# skware-one-rev-arm-25-mini.net
KiCad netlist of a schematic drawn in EAGLE
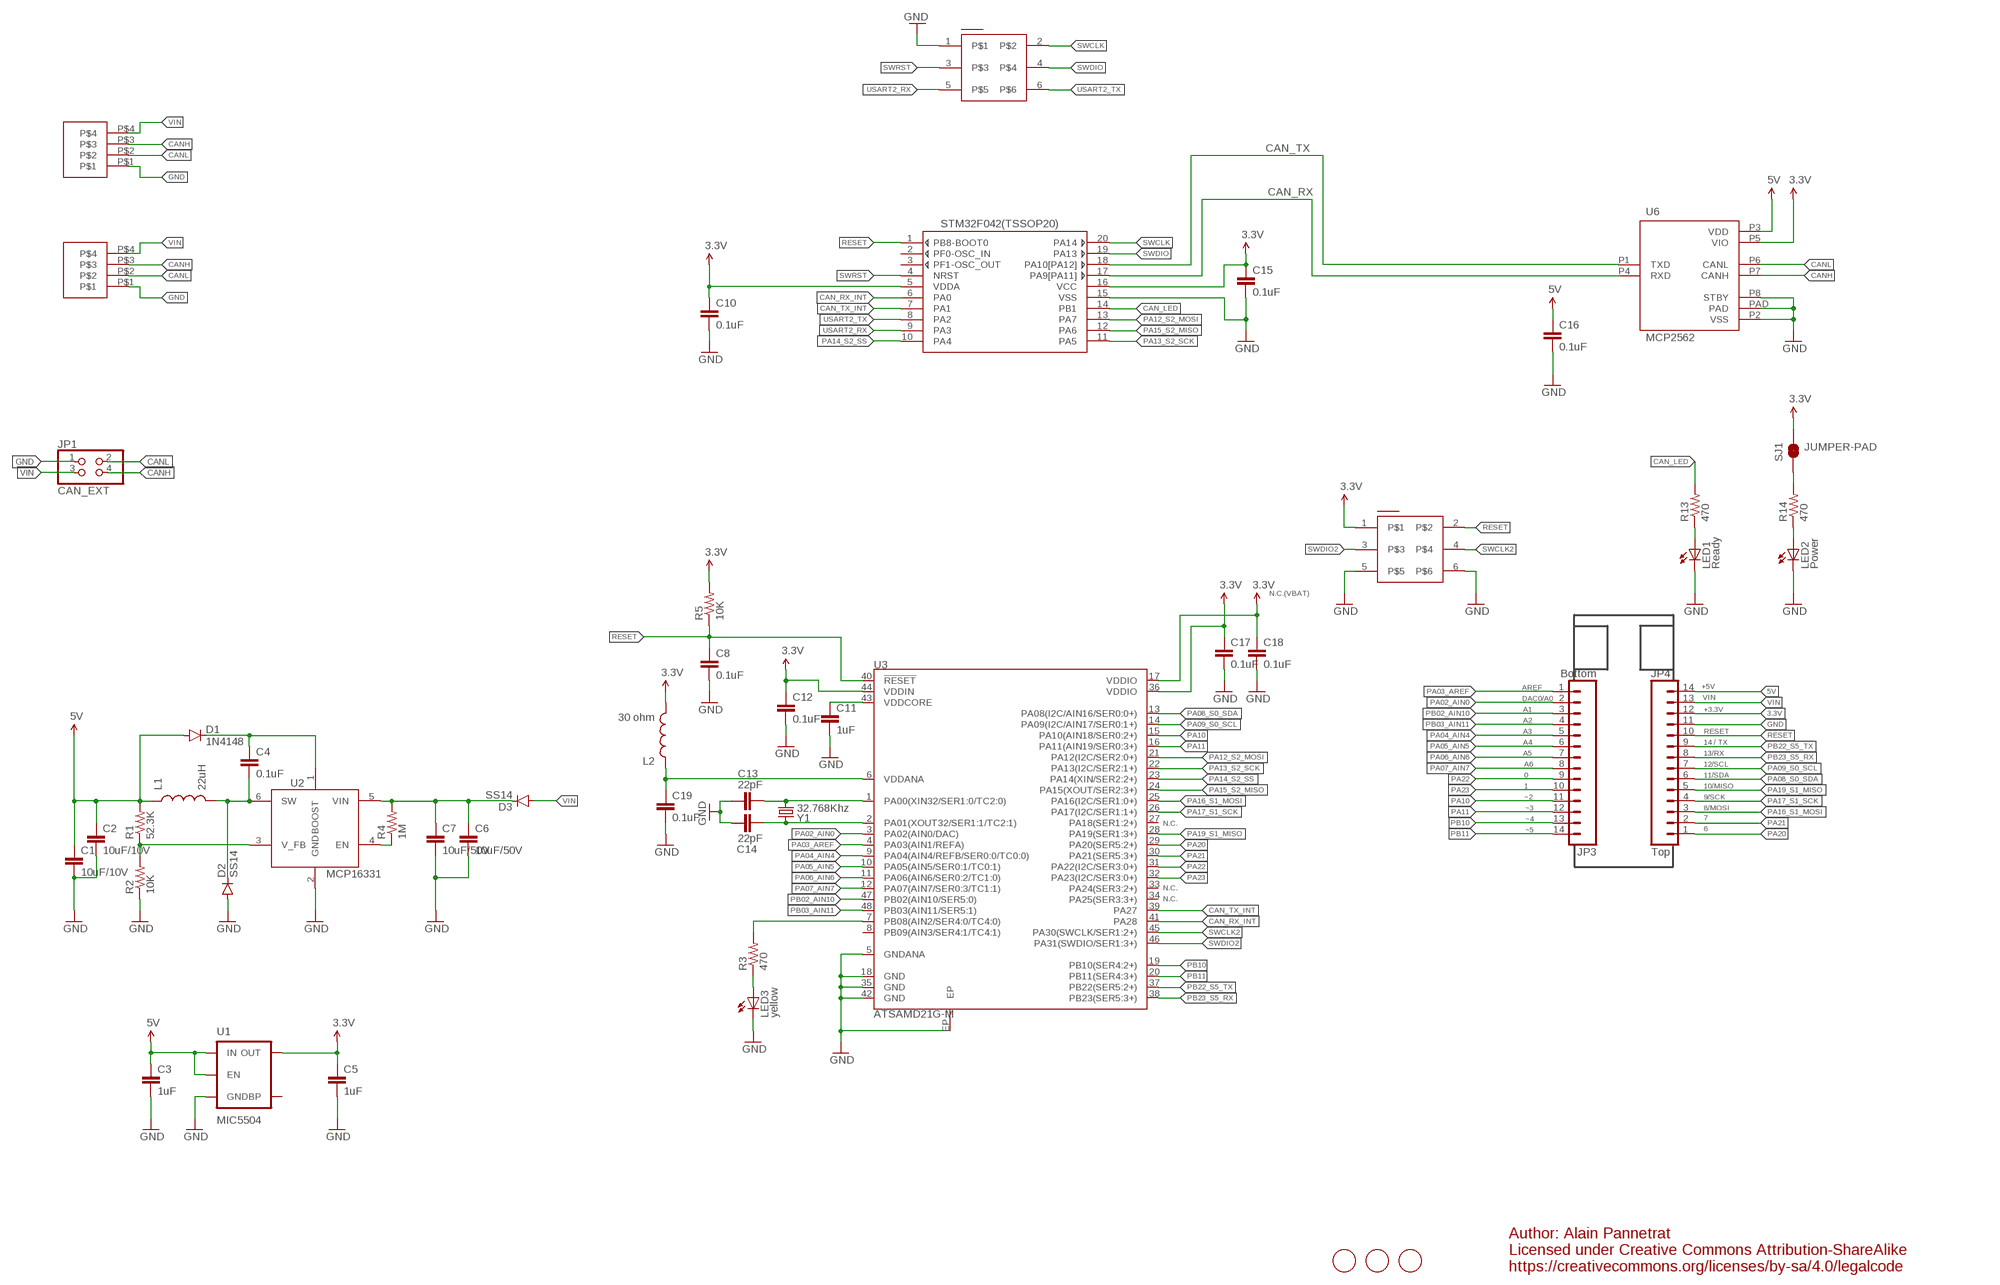
[diagram p0: schematic, sheet 1]

(export (version "E")
  (design (tool "Eeschema 10.0.6"))
  (components
    (comp (ref "C1")
      (value "10uF/10V")
      (footprint "eagle-import:0805")
      (libsource (lib "eagle-import") (part "CAP0805"))
    )
    (comp (ref "C2")
      (value "10uF/10V")
      (footprint "eagle-import:0805")
      (libsource (lib "eagle-import") (part "CAP0805"))
    )
    (comp (ref "C3")
      (value "1uF")
      (footprint "eagle-import:0805")
      (libsource (lib "eagle-import") (part "CAP0805"))
    )
    (comp (ref "C4")
      (value "0.1uF")
      (footprint "eagle-import:0603-CAP")
      (libsource (lib "eagle-import") (part "SparkFun-Passives_CAP0603-CAP"))
    )
    (comp (ref "C5")
      (value "1uF")
      (footprint "eagle-import:0805")
      (libsource (lib "eagle-import") (part "CAP0805"))
    )
    (comp (ref "C6")
      (value "10uF/50V")
      (footprint "eagle-import:1206")
      (libsource (lib "eagle-import") (part "CAP1206"))
    )
    (comp (ref "C7")
      (value "10uF/50V")
      (footprint "eagle-import:1206")
      (libsource (lib "eagle-import") (part "CAP1206"))
    )
    (comp (ref "C8")
      (value "0.1uF")
      (footprint "eagle-import:0603-CAP")
      (libsource (lib "eagle-import") (part "SparkFun-Passives_CAP0603-CAP"))
    )
    (comp (ref "C10")
      (value "0.1uF")
      (footprint "eagle-import:0603-CAP")
      (libsource (lib "eagle-import") (part "SparkFun-Passives_CAP0603-CAP"))
    )
    (comp (ref "C11")
      (value "1uF")
      (footprint "eagle-import:0805")
      (libsource (lib "eagle-import") (part "SparkFun-Passives_CAP0805"))
    )
    (comp (ref "C12")
      (value "0.1uF")
      (footprint "eagle-import:0603-CAP")
      (libsource (lib "eagle-import") (part "SparkFun-Passives_CAP0603-CAP"))
    )
    (comp (ref "C13")
      (value "22pF")
      (footprint "eagle-import:0805")
      (libsource (lib "eagle-import") (part "SparkFun-Passives_CAP0805"))
    )
    (comp (ref "C14")
      (value "22pF")
      (footprint "eagle-import:0805")
      (libsource (lib "eagle-import") (part "SparkFun-Passives_CAP0805"))
    )
    (comp (ref "C15")
      (value "0.1uF")
      (footprint "eagle-import:0603-CAP")
      (libsource (lib "eagle-import") (part "SparkFun-Passives_CAP0603-CAP"))
    )
    (comp (ref "C16")
      (value "0.1uF")
      (footprint "eagle-import:0603-CAP")
      (libsource (lib "eagle-import") (part "SparkFun-Passives_CAP0603-CAP"))
    )
    (comp (ref "C17")
      (value "0.1uF")
      (footprint "eagle-import:0603-CAP")
      (libsource (lib "eagle-import") (part "SparkFun-Passives_CAP0603-CAP"))
    )
    (comp (ref "C18")
      (value "0.1uF")
      (footprint "eagle-import:0603-CAP")
      (libsource (lib "eagle-import") (part "SparkFun-Passives_CAP0603-CAP"))
    )
    (comp (ref "C19")
      (value "0.1uF")
      (footprint "eagle-import:0603-CAP")
      (libsource (lib "eagle-import") (part "SparkFun-Passives_CAP0603-CAP"))
    )
    (comp (ref "D1")
      (value "1N4148")
      (footprint "eagle-import:SOD-323")
      (libsource (lib "eagle-import") (part "DIODEBAS16"))
    )
    (comp (ref "D2")
      (value "SS14")
      (footprint "eagle-import:SMA-DIODE_ALT")
      (libsource (lib "eagle-import") (part "DIODESMA-ALT"))
    )
    (comp (ref "D3")
      (value "SS14")
      (footprint "eagle-import:SMA-DIODE_ALT")
      (libsource (lib "eagle-import") (part "DIODESMA-ALT"))
    )
    (comp (ref "JP1")
      (value "CAN_EXT")
      (footprint "eagle-import:2X02")
      (libsource (lib "eagle-import") (part "PINHD-2X2"))
    )
    (comp (ref "JP3")
      (value "Bottom")
      (footprint "eagle-import:1X14")
      (libsource (lib "eagle-import") (part "M14"))
    )
    (comp (ref "JP4")
      (value "Top")
      (footprint "eagle-import:1X14")
      (libsource (lib "eagle-import") (part "M14"))
    )
    (comp (ref "L1")
      (value "22uH")
      (footprint "eagle-import:SRN6045")
      (libsource (lib "eagle-import") (part "INDUCTORBOURNS_SRN6045"))
    )
    (comp (ref "L2")
      (value "30 ohm")
      (footprint "eagle-import:0603")
      (libsource (lib "eagle-import") (part "INDUCTOR30OHM,1.8A"))
    )
    (comp (ref "LED1")
      (value "Ready")
      (footprint "eagle-import:SML0805")
      (libsource (lib "eagle-import") (part "LEDSML0805"))
    )
    (comp (ref "LED2")
      (value "Power")
      (footprint "eagle-import:SML0805")
      (libsource (lib "eagle-import") (part "LEDSML0805"))
    )
    (comp (ref "LED3")
      (value "yellow")
      (footprint "eagle-import:SML0805")
      (libsource (lib "eagle-import") (part "LEDSML0805"))
    )
    (comp (ref "R1")
      (value "52.3K")
      (footprint "eagle-import:0805")
      (libsource (lib "eagle-import") (part "RESISTOR0805-RES"))
    )
    (comp (ref "R2")
      (value "10K")
      (footprint "eagle-import:0805")
      (libsource (lib "eagle-import") (part "RESISTOR0805-RES"))
    )
    (comp (ref "R3")
      (value "470")
      (footprint "eagle-import:0603-RES")
      (libsource (lib "eagle-import") (part "RESISTOR0603-RES"))
    )
    (comp (ref "R4")
      (value "1M")
      (footprint "eagle-import:0805")
      (libsource (lib "eagle-import") (part "RESISTOR0805-RES"))
    )
    (comp (ref "R5")
      (value "10K")
      (footprint "eagle-import:0805")
      (libsource (lib "eagle-import") (part "RESISTOR0805-RES"))
    )
    (comp (ref "R13")
      (value "470")
      (footprint "eagle-import:0603-RES")
      (libsource (lib "eagle-import") (part "RESISTOR0603-RES"))
    )
    (comp (ref "R14")
      (value "470")
      (footprint "eagle-import:0603-RES")
      (libsource (lib "eagle-import") (part "RESISTOR0603-RES"))
    )
    (comp (ref "SJ1")
      (value "JUMPER-PAD")
      (footprint "eagle-import:PAD-JUMPER-2-NC_BY_TRACE_YES_SILK")
      (libsource (lib "eagle-import") (part "JUMPER-PAD-2-NC_BY_TRACE"))
    )
    (comp (ref "U$1")
      (value "M04-PLUG-3.5")
      (footprint "eagle-import:M04-PLUG-3.5")
      (libsource (lib "eagle-import") (part "M04-PLUG-3.5"))
    )
    (comp (ref "U$3")
      (value "M04-PLUG-3.5")
      (footprint "eagle-import:M04-PLUG-3.5")
      (libsource (lib "eagle-import") (part "M04-PLUG-3.5"))
    )
    (comp (ref "U$4")
      (value "3X2-SMT-PROG")
      (footprint "eagle-import:2X3-SMT-HEAD")
      (libsource (lib "eagle-import") (part "3X2-SMT-PROG"))
    )
    (comp (ref "U$5")
      (value "3X2-SMT-PROG")
      (footprint "eagle-import:2X3-SMT-HEAD")
      (libsource (lib "eagle-import") (part "3X2-SMT-PROG"))
    )
    (comp (ref "U$6")
      (value "FIDUCIAL")
      (footprint "eagle-import:FIDUCIAL_1MM")
      (libsource (lib "eagle-import") (part "FIDUCIAL"))
    )
    (comp (ref "U$7")
      (value "FIDUCIAL")
      (footprint "eagle-import:FIDUCIAL_1MM")
      (libsource (lib "eagle-import") (part "FIDUCIAL"))
    )
    (comp (ref "U$8")
      (value "FIDUCIAL")
      (footprint "eagle-import:FIDUCIAL_1MM")
      (libsource (lib "eagle-import") (part "FIDUCIAL"))
    )
    (comp (ref "U1")
      (value "MIC5504")
      (footprint "eagle-import:SOT23-5")
      (libsource (lib "eagle-import") (part "V_REG_LDOSMD"))
    )
    (comp (ref "U2")
      (value "MCP16331")
      (footprint "eagle-import:SOT23-6")
      (libsource (lib "eagle-import") (part "MCP16331"))
    )
    (comp (ref "U3")
      (value "ATSAMD21G-M")
      (footprint "eagle-import:QFN-48")
      (libsource (lib "eagle-import") (part "ATSAMD21G-M"))
    )
    (comp (ref "U4")
      (value "STM32F042(TSSOP20)")
      (footprint "eagle-import:TSSOP20")
      (libsource (lib "eagle-import") (part "STM32F042(TSSOP20)"))
    )
    (comp (ref "U6")
      (value "MCP2562")
      (footprint "eagle-import:DFN3X3")
      (libsource (lib "eagle-import") (part "MCP2562"))
    )
    (comp (ref "Y1")
      (value "32.768Khz")
      (footprint "eagle-import:CRYSTAL-SMD-3.2X1.5MM")
      (libsource (lib "eagle-import") (part "CRYSTAL3.2X1.5MM"))
    )
  )
  (nets
    (net (code "1") (name "/CAN_RX") (class "Default")
      (node (ref "U4") (pin "17") (pinfunction "PA9[PA11]_17") (pintype "bidirectional"))
      (node (ref "U6") (pin "P4") (pinfunction "RXD_P4") (pintype "bidirectional"))
    )
    (net (code "2") (name "/CAN_TX") (class "Default")
      (node (ref "U4") (pin "18") (pinfunction "PA10[PA12]_18") (pintype "bidirectional"))
      (node (ref "U6") (pin "P1") (pinfunction "TXD_P1") (pintype "bidirectional"))
    )
    (net (code "3") (name "3.3V") (class "Default")
      (node (ref "C10") (pin "1") (pinfunction "1_1") (pintype "passive"))
      (node (ref "C12") (pin "1") (pinfunction "1_1") (pintype "passive"))
      (node (ref "C15") (pin "1") (pinfunction "1_1") (pintype "passive"))
      (node (ref "C17") (pin "1") (pinfunction "1_1") (pintype "passive"))
      (node (ref "C18") (pin "1") (pinfunction "1_1") (pintype "passive"))
      (node (ref "C5") (pin "1") (pinfunction "1_1") (pintype "passive"))
      (node (ref "JP4") (pin "12") (pinfunction "12_12") (pintype "passive"))
      (node (ref "L2") (pin "2") (pinfunction "2_2") (pintype "passive"))
      (node (ref "R5") (pin "2") (pinfunction "2_2") (pintype "passive"))
      (node (ref "SJ1") (pin "2") (pinfunction "2_2") (pintype "passive"))
      (node (ref "U$4") (pin "1") (pinfunction "P$1_1") (pintype "bidirectional"))
      (node (ref "U1") (pin "5") (pinfunction "OUT_5") (pintype "passive"))
      (node (ref "U3") (pin "17") (pinfunction "VDDIO_17") (pintype "bidirectional"))
      (node (ref "U3") (pin "36") (pinfunction "VDDIO_36") (pintype "bidirectional"))
      (node (ref "U3") (pin "44") (pinfunction "VDDIN_44") (pintype "bidirectional"))
      (node (ref "U4") (pin "16") (pinfunction "VCC_16") (pintype "power_in"))
      (node (ref "U4") (pin "5") (pinfunction "VDDA_5") (pintype "power_in"))
      (node (ref "U6") (pin "P5") (pinfunction "VIO_P5") (pintype "bidirectional"))
    )
    (net (code "4") (name "5V") (class "Default")
      (node (ref "C1") (pin "1") (pinfunction "1_1") (pintype "passive"))
      (node (ref "C16") (pin "1") (pinfunction "1_1") (pintype "passive"))
      (node (ref "C2") (pin "1") (pinfunction "1_1") (pintype "passive"))
      (node (ref "C3") (pin "1") (pinfunction "1_1") (pintype "passive"))
      (node (ref "D1") (pin "A") (pinfunction "A_A") (pintype "passive"))
      (node (ref "JP4") (pin "14") (pinfunction "14_14") (pintype "passive"))
      (node (ref "L1") (pin "1") (pinfunction "1_1") (pintype "passive"))
      (node (ref "R1") (pin "2") (pinfunction "2_2") (pintype "passive"))
      (node (ref "U1") (pin "1") (pinfunction "IN_1") (pintype "input"))
      (node (ref "U1") (pin "3") (pinfunction "EN_3") (pintype "input"))
      (node (ref "U6") (pin "P3") (pinfunction "VDD_P3") (pintype "bidirectional"))
    )
    (net (code "5") (name "CANH") (class "Default")
      (node (ref "JP1") (pin "4") (pinfunction "4_4") (pintype "passive"))
      (node (ref "U$1") (pin "P$3") (pinfunction "P$3_P$3") (pintype "bidirectional"))
      (node (ref "U$3") (pin "P$3") (pinfunction "P$3_P$3") (pintype "bidirectional"))
      (node (ref "U6") (pin "P7") (pinfunction "CANH_P7") (pintype "bidirectional"))
    )
    (net (code "6") (name "CANL") (class "Default")
      (node (ref "JP1") (pin "2") (pinfunction "2_2") (pintype "passive"))
      (node (ref "U$1") (pin "P$2") (pinfunction "P$2_P$2") (pintype "bidirectional"))
      (node (ref "U$3") (pin "P$2") (pinfunction "P$2_P$2") (pintype "bidirectional"))
      (node (ref "U6") (pin "P6") (pinfunction "CANL_P6") (pintype "bidirectional"))
    )
    (net (code "7") (name "CAN_LED") (class "Default")
      (node (ref "R13") (pin "2") (pinfunction "2_2") (pintype "passive"))
      (node (ref "U4") (pin "14") (pinfunction "PB1_14") (pintype "bidirectional"))
    )
    (net (code "8") (name "CAN_RX_INT") (class "Default")
      (node (ref "U3") (pin "41") (pinfunction "PA28_41") (pintype "bidirectional"))
      (node (ref "U4") (pin "6") (pinfunction "PA0_6") (pintype "bidirectional"))
    )
    (net (code "9") (name "CAN_TX_INT") (class "Default")
      (node (ref "U3") (pin "39") (pinfunction "PA27_39") (pintype "bidirectional"))
      (node (ref "U4") (pin "7") (pinfunction "PA1_7") (pintype "bidirectional"))
    )
    (net (code "10") (name "GND") (class "Default")
      (node (ref "C1") (pin "2") (pinfunction "2_2") (pintype "passive"))
      (node (ref "C10") (pin "2") (pinfunction "2_2") (pintype "passive"))
      (node (ref "C11") (pin "2") (pinfunction "2_2") (pintype "passive"))
      (node (ref "C12") (pin "2") (pinfunction "2_2") (pintype "passive"))
      (node (ref "C13") (pin "1") (pinfunction "1_1") (pintype "passive"))
      (node (ref "C14") (pin "1") (pinfunction "1_1") (pintype "passive"))
      (node (ref "C15") (pin "2") (pinfunction "2_2") (pintype "passive"))
      (node (ref "C16") (pin "2") (pinfunction "2_2") (pintype "passive"))
      (node (ref "C17") (pin "2") (pinfunction "2_2") (pintype "passive"))
      (node (ref "C18") (pin "2") (pinfunction "2_2") (pintype "passive"))
      (node (ref "C19") (pin "2") (pinfunction "2_2") (pintype "passive"))
      (node (ref "C2") (pin "2") (pinfunction "2_2") (pintype "passive"))
      (node (ref "C3") (pin "2") (pinfunction "2_2") (pintype "passive"))
      (node (ref "C5") (pin "2") (pinfunction "2_2") (pintype "passive"))
      (node (ref "C6") (pin "2") (pinfunction "2_2") (pintype "passive"))
      (node (ref "C7") (pin "2") (pinfunction "2_2") (pintype "passive"))
      (node (ref "C8") (pin "2") (pinfunction "2_2") (pintype "passive"))
      (node (ref "D2") (pin "A") (pinfunction "A_A") (pintype "passive"))
      (node (ref "JP1") (pin "1") (pinfunction "1_1") (pintype "passive"))
      (node (ref "JP4") (pin "11") (pinfunction "11_11") (pintype "passive"))
      (node (ref "LED1") (pin "C") (pinfunction "C_C") (pintype "passive"))
      (node (ref "LED2") (pin "C") (pinfunction "C_C") (pintype "passive"))
      (node (ref "LED3") (pin "C") (pinfunction "C_C") (pintype "passive"))
      (node (ref "R2") (pin "1") (pinfunction "1_1") (pintype "passive"))
      (node (ref "U$1") (pin "P$1") (pinfunction "P$1_P$1") (pintype "bidirectional"))
      (node (ref "U$3") (pin "P$1") (pinfunction "P$1_P$1") (pintype "bidirectional"))
      (node (ref "U$4") (pin "5") (pinfunction "P$5_5") (pintype "bidirectional"))
      (node (ref "U$4") (pin "6") (pinfunction "P$6_6") (pintype "bidirectional"))
      (node (ref "U$5") (pin "1") (pinfunction "P$1_1") (pintype "bidirectional"))
      (node (ref "U1") (pin "2") (pinfunction "GND_2") (pintype "input"))
      (node (ref "U2") (pin "2") (pinfunction "GND_2") (pintype "power_in"))
      (node (ref "U3") (pin "18") (pinfunction "GND_18") (pintype "bidirectional"))
      (node (ref "U3") (pin "35") (pinfunction "GND_35") (pintype "bidirectional"))
      (node (ref "U3") (pin "42") (pinfunction "GND_42") (pintype "bidirectional"))
      (node (ref "U3") (pin "5") (pinfunction "GNDANA_5") (pintype "bidirectional"))
      (node (ref "U3") (pin "EP") (pinfunction "EP_EP") (pintype "bidirectional"))
      (node (ref "U4") (pin "15") (pinfunction "VSS_15") (pintype "power_in"))
      (node (ref "U6") (pin "P2") (pinfunction "VSS_P2") (pintype "bidirectional"))
      (node (ref "U6") (pin "P8") (pinfunction "STBY_P8") (pintype "bidirectional"))
      (node (ref "U6") (pin "PAD") (pinfunction "PAD_PAD") (pintype "bidirectional"))
    )
    (net (code "11") (name "Net-(LED1-PadA)") (class "Default")
      (node (ref "LED1") (pin "A") (pinfunction "A_A") (pintype "passive"))
      (node (ref "R13") (pin "1") (pinfunction "1_1") (pintype "passive"))
    )
    (net (code "12") (name "Net-(LED2-PadA)") (class "Default")
      (node (ref "LED2") (pin "A") (pinfunction "A_A") (pintype "passive"))
      (node (ref "R14") (pin "1") (pinfunction "1_1") (pintype "passive"))
    )
    (net (code "13") (name "Net-(LED3-PadA)") (class "Default")
      (node (ref "LED3") (pin "A") (pinfunction "A_A") (pintype "passive"))
      (node (ref "R3") (pin "1") (pinfunction "1_1") (pintype "passive"))
    )
    (net (code "14") (name "Net-(R14-Pad2)") (class "Default")
      (node (ref "R14") (pin "2") (pinfunction "2_2") (pintype "passive"))
      (node (ref "SJ1") (pin "1") (pinfunction "1_1") (pintype "passive"))
    )
    (net (code "15") (name "Net-(U2-BOOST)") (class "Default")
      (node (ref "C4") (pin "1") (pinfunction "1_1") (pintype "passive"))
      (node (ref "D1") (pin "C") (pinfunction "C_C") (pintype "passive"))
      (node (ref "U2") (pin "1") (pinfunction "BOOST_1") (pintype "passive"))
    )
    (net (code "16") (name "Net-(U2-EN)") (class "Default")
      (node (ref "R4") (pin "1") (pinfunction "1_1") (pintype "passive"))
      (node (ref "U2") (pin "4") (pinfunction "EN_4") (pintype "input"))
    )
    (net (code "17") (name "Net-(U2-SW)") (class "Default")
      (node (ref "C4") (pin "2") (pinfunction "2_2") (pintype "passive"))
      (node (ref "D2") (pin "C") (pinfunction "C_C") (pintype "passive"))
      (node (ref "L1") (pin "2") (pinfunction "2_2") (pintype "passive"))
      (node (ref "U2") (pin "6") (pinfunction "SW_6") (pintype "power_in"))
    )
    (net (code "18") (name "Net-(U2-VIN)") (class "Default")
      (node (ref "C6") (pin "1") (pinfunction "1_1") (pintype "passive"))
      (node (ref "C7") (pin "1") (pinfunction "1_1") (pintype "passive"))
      (node (ref "D3") (pin "C") (pinfunction "C_C") (pintype "passive"))
      (node (ref "R4") (pin "2") (pinfunction "2_2") (pintype "passive"))
      (node (ref "U2") (pin "5") (pinfunction "VIN_5") (pintype "power_in"))
    )
    (net (code "19") (name "Net-(U2-V_FB)") (class "Default")
      (node (ref "R1") (pin "1") (pinfunction "1_1") (pintype "passive"))
      (node (ref "R2") (pin "2") (pinfunction "2_2") (pintype "passive"))
      (node (ref "U2") (pin "3") (pinfunction "V_FB_3") (pintype "input"))
    )
    (net (code "20") (name "Net-(U3-PA00(XIN32{slash}SER1:0{slash}TC2:0))") (class "Default")
      (node (ref "C13") (pin "2") (pinfunction "2_2") (pintype "passive"))
      (node (ref "U3") (pin "1") (pinfunction "PA00(XIN32/SER1:0/TC2:0)_1") (pintype "bidirectional"))
      (node (ref "Y1") (pin "P$2") (pinfunction "2_P$2") (pintype "passive"))
    )
    (net (code "21") (name "Net-(U3-PA01(XOUT32{slash}SER1:1{slash}TC2:1))") (class "Default")
      (node (ref "C14") (pin "2") (pinfunction "2_2") (pintype "passive"))
      (node (ref "U3") (pin "2") (pinfunction "PA01(XOUT32/SER1:1/TC2:1)_2") (pintype "bidirectional"))
      (node (ref "Y1") (pin "P$1") (pinfunction "1_P$1") (pintype "passive"))
    )
    (net (code "22") (name "Net-(U3-PB08(AIN2{slash}SER4:0{slash}TC4:0))") (class "Default")
      (node (ref "R3") (pin "2") (pinfunction "2_2") (pintype "passive"))
      (node (ref "U3") (pin "7") (pinfunction "PB08(AIN2/SER4:0/TC4:0)_7") (pintype "bidirectional"))
    )
    (net (code "23") (name "Net-(U3-VDDANA)") (class "Default")
      (node (ref "C19") (pin "1") (pinfunction "1_1") (pintype "passive"))
      (node (ref "L2") (pin "1") (pinfunction "1_1") (pintype "passive"))
      (node (ref "U3") (pin "6") (pinfunction "VDDANA_6") (pintype "bidirectional"))
    )
    (net (code "24") (name "Net-(U3-VDDCORE)") (class "Default")
      (node (ref "C11") (pin "1") (pinfunction "1_1") (pintype "passive"))
      (node (ref "U3") (pin "43") (pinfunction "VDDCORE_43") (pintype "bidirectional"))
    )
    (net (code "25") (name "PA02_AIN0") (class "Default")
      (node (ref "JP3") (pin "2") (pinfunction "2_2") (pintype "passive"))
      (node (ref "U3") (pin "3") (pinfunction "PA02(AIN0/DAC)_3") (pintype "bidirectional"))
    )
    (net (code "26") (name "PA03_AREF") (class "Default")
      (node (ref "JP3") (pin "1") (pinfunction "1_1") (pintype "passive"))
      (node (ref "U3") (pin "4") (pinfunction "PA03(AIN1/REFA)_4") (pintype "bidirectional"))
    )
    (net (code "27") (name "PA04_AIN4") (class "Default")
      (node (ref "JP3") (pin "5") (pinfunction "5_5") (pintype "passive"))
      (node (ref "U3") (pin "9") (pinfunction "PA04(AIN4/REFB/SER0:0/TC0:0)_9") (pintype "bidirectional"))
    )
    (net (code "28") (name "PA05_AIN5") (class "Default")
      (node (ref "JP3") (pin "6") (pinfunction "6_6") (pintype "passive"))
      (node (ref "U3") (pin "10") (pinfunction "PA05(AIN5/SER0:1/TC0:1)_10") (pintype "bidirectional"))
    )
    (net (code "29") (name "PA06_AIN6") (class "Default")
      (node (ref "JP3") (pin "7") (pinfunction "7_7") (pintype "passive"))
      (node (ref "U3") (pin "11") (pinfunction "PA06(AIN6/SER0:2/TC1:0)_11") (pintype "bidirectional"))
    )
    (net (code "30") (name "PA07_AIN7") (class "Default")
      (node (ref "JP3") (pin "8") (pinfunction "8_8") (pintype "passive"))
      (node (ref "U3") (pin "12") (pinfunction "PA07(AIN7/SER0:3/TC1:1)_12") (pintype "bidirectional"))
    )
    (net (code "31") (name "PA08_S0_SDA") (class "Default")
      (node (ref "JP4") (pin "6") (pinfunction "6_6") (pintype "passive"))
      (node (ref "U3") (pin "13") (pinfunction "PA08(I2C/AIN16/SER0:0+)_13") (pintype "bidirectional"))
    )
    (net (code "32") (name "PA09_S0_SCL") (class "Default")
      (node (ref "JP4") (pin "7") (pinfunction "7_7") (pintype "passive"))
      (node (ref "U3") (pin "14") (pinfunction "PA09(I2C/AIN17/SER0:1+)_14") (pintype "bidirectional"))
    )
    (net (code "33") (name "PA10") (class "Default")
      (node (ref "JP3") (pin "11") (pinfunction "11_11") (pintype "passive"))
      (node (ref "U3") (pin "15") (pinfunction "PA10(AIN18/SER0:2+)_15") (pintype "bidirectional"))
    )
    (net (code "34") (name "PA11") (class "Default")
      (node (ref "JP3") (pin "12") (pinfunction "12_12") (pintype "passive"))
      (node (ref "U3") (pin "16") (pinfunction "PA11(AIN19/SER0:3+)_16") (pintype "bidirectional"))
    )
    (net (code "35") (name "PA12_S2_MOSI") (class "Default")
      (node (ref "U3") (pin "21") (pinfunction "PA12(I2C/SER2:0+)_21") (pintype "bidirectional"))
      (node (ref "U4") (pin "13") (pinfunction "PA7_13") (pintype "bidirectional"))
    )
    (net (code "36") (name "PA13_S2_SCK") (class "Default")
      (node (ref "U3") (pin "22") (pinfunction "PA13(I2C/SER2:1+)_22") (pintype "bidirectional"))
      (node (ref "U4") (pin "11") (pinfunction "PA5_11") (pintype "bidirectional"))
    )
    (net (code "37") (name "PA14_S2_SS") (class "Default")
      (node (ref "U3") (pin "23") (pinfunction "PA14(XIN/SER2:2+)_23") (pintype "bidirectional"))
      (node (ref "U4") (pin "10") (pinfunction "PA4_10") (pintype "bidirectional"))
    )
    (net (code "38") (name "PA15_S2_MISO") (class "Default")
      (node (ref "U3") (pin "24") (pinfunction "PA15(XOUT/SER2:3+)_24") (pintype "bidirectional"))
      (node (ref "U4") (pin "12") (pinfunction "PA6_12") (pintype "bidirectional"))
    )
    (net (code "39") (name "PA16_S1_MOSI") (class "Default")
      (node (ref "JP4") (pin "3") (pinfunction "3_3") (pintype "passive"))
      (node (ref "U3") (pin "25") (pinfunction "PA16(I2C/SER1:0+)_25") (pintype "bidirectional"))
    )
    (net (code "40") (name "PA17_S1_SCK") (class "Default")
      (node (ref "JP4") (pin "4") (pinfunction "4_4") (pintype "passive"))
      (node (ref "U3") (pin "26") (pinfunction "PA17(I2C/SER1:1+)_26") (pintype "bidirectional"))
    )
    (net (code "41") (name "PA19_S1_MISO") (class "Default")
      (node (ref "JP4") (pin "5") (pinfunction "5_5") (pintype "passive"))
      (node (ref "U3") (pin "28") (pinfunction "PA19(SER1:3+)_28") (pintype "bidirectional"))
    )
    (net (code "42") (name "PA20") (class "Default")
      (node (ref "JP4") (pin "1") (pinfunction "1_1") (pintype "passive"))
      (node (ref "U3") (pin "29") (pinfunction "PA20(SER5:2+)_29") (pintype "bidirectional"))
    )
    (net (code "43") (name "PA21") (class "Default")
      (node (ref "JP4") (pin "2") (pinfunction "2_2") (pintype "passive"))
      (node (ref "U3") (pin "30") (pinfunction "PA21(SER5:3+)_30") (pintype "bidirectional"))
    )
    (net (code "44") (name "PA22") (class "Default")
      (node (ref "JP3") (pin "9") (pinfunction "9_9") (pintype "passive"))
      (node (ref "U3") (pin "31") (pinfunction "PA22(I2C/SER3:0+)_31") (pintype "bidirectional"))
    )
    (net (code "45") (name "PA23") (class "Default")
      (node (ref "JP3") (pin "10") (pinfunction "10_10") (pintype "passive"))
      (node (ref "U3") (pin "32") (pinfunction "PA23(I2C/SER3:0+)_32") (pintype "bidirectional"))
    )
    (net (code "46") (name "PB02_AIN10") (class "Default")
      (node (ref "JP3") (pin "3") (pinfunction "3_3") (pintype "passive"))
      (node (ref "U3") (pin "47") (pinfunction "PB02(AIN10/SER5:0)_47") (pintype "bidirectional"))
    )
    (net (code "47") (name "PB03_AIN11") (class "Default")
      (node (ref "JP3") (pin "4") (pinfunction "4_4") (pintype "passive"))
      (node (ref "U3") (pin "48") (pinfunction "PB03(AIN11/SER5:1)_48") (pintype "bidirectional"))
    )
    (net (code "48") (name "PB10") (class "Default")
      (node (ref "JP3") (pin "13") (pinfunction "13_13") (pintype "passive"))
      (node (ref "U3") (pin "19") (pinfunction "PB10(SER4:2+)_19") (pintype "bidirectional"))
    )
    (net (code "49") (name "PB11") (class "Default")
      (node (ref "JP3") (pin "14") (pinfunction "14_14") (pintype "passive"))
      (node (ref "U3") (pin "20") (pinfunction "PB11(SER4:3+)_20") (pintype "bidirectional"))
    )
    (net (code "50") (name "PB22_S5_TX") (class "Default")
      (node (ref "JP4") (pin "9") (pinfunction "9_9") (pintype "passive"))
      (node (ref "U3") (pin "37") (pinfunction "PB22(SER5:2+)_37") (pintype "bidirectional"))
    )
    (net (code "51") (name "PB23_S5_RX") (class "Default")
      (node (ref "JP4") (pin "8") (pinfunction "8_8") (pintype "passive"))
      (node (ref "U3") (pin "38") (pinfunction "PB23(SER5:3+)_38") (pintype "bidirectional"))
    )
    (net (code "52") (name "RESET") (class "Default")
      (node (ref "C8") (pin "1") (pinfunction "1_1") (pintype "passive"))
      (node (ref "JP4") (pin "10") (pinfunction "10_10") (pintype "passive"))
      (node (ref "R5") (pin "1") (pinfunction "1_1") (pintype "passive"))
      (node (ref "U$4") (pin "2") (pinfunction "P$2_2") (pintype "bidirectional"))
      (node (ref "U3") (pin "40") (pinfunction "~{RESET}_40") (pintype "bidirectional"))
      (node (ref "U4") (pin "1") (pinfunction "PB8-BOOT0_1") (pintype "bidirectional"))
    )
    (net (code "53") (name "SWCLK") (class "Default")
      (node (ref "U$5") (pin "2") (pinfunction "P$2_2") (pintype "bidirectional"))
      (node (ref "U4") (pin "20") (pinfunction "PA14_20") (pintype "bidirectional"))
    )
    (net (code "54") (name "SWCLK2") (class "Default")
      (node (ref "U$4") (pin "4") (pinfunction "P$4_4") (pintype "bidirectional"))
      (node (ref "U3") (pin "45") (pinfunction "PA30(SWCLK/SER1:2+)_45") (pintype "bidirectional"))
    )
    (net (code "55") (name "SWDIO") (class "Default")
      (node (ref "U$5") (pin "4") (pinfunction "P$4_4") (pintype "bidirectional"))
      (node (ref "U4") (pin "19") (pinfunction "PA13_19") (pintype "bidirectional"))
    )
    (net (code "56") (name "SWDIO2") (class "Default")
      (node (ref "U$4") (pin "3") (pinfunction "P$3_3") (pintype "bidirectional"))
      (node (ref "U3") (pin "46") (pinfunction "PA31(SWDIO/SER1:3+)_46") (pintype "bidirectional"))
    )
    (net (code "57") (name "SWRST") (class "Default")
      (node (ref "U$5") (pin "3") (pinfunction "P$3_3") (pintype "bidirectional"))
      (node (ref "U4") (pin "4") (pinfunction "NRST_4") (pintype "bidirectional"))
    )
    (net (code "58") (name "USART2_RX") (class "Default")
      (node (ref "U$5") (pin "5") (pinfunction "P$5_5") (pintype "bidirectional"))
      (node (ref "U4") (pin "9") (pinfunction "PA3_9") (pintype "bidirectional"))
    )
    (net (code "59") (name "USART2_TX") (class "Default")
      (node (ref "U$5") (pin "6") (pinfunction "P$6_6") (pintype "bidirectional"))
      (node (ref "U4") (pin "8") (pinfunction "PA2_8") (pintype "bidirectional"))
    )
    (net (code "60") (name "VIN") (class "Default")
      (node (ref "D3") (pin "A") (pinfunction "A_A") (pintype "passive"))
      (node (ref "JP1") (pin "3") (pinfunction "3_3") (pintype "passive"))
      (node (ref "JP4") (pin "13") (pinfunction "13_13") (pintype "passive"))
      (node (ref "U$1") (pin "P$4") (pinfunction "P$4_P$4") (pintype "bidirectional"))
      (node (ref "U$3") (pin "P$4") (pinfunction "P$4_P$4") (pintype "bidirectional"))
    )
    (net (code "61") (name "unconnected-(U1-BP-Pad4)") (class "Default")
      (node (ref "U1") (pin "4") (pinfunction "BP_4") (pintype "input"))
    )
    (net (code "62") (name "unconnected-(U3-PA18(SER1:2+)-Pad27)") (class "Default")
      (node (ref "U3") (pin "27") (pinfunction "PA18(SER1:2+)_27") (pintype "bidirectional"))
    )
    (net (code "63") (name "unconnected-(U3-PA24(SER3:2+)-Pad33)") (class "Default")
      (node (ref "U3") (pin "33") (pinfunction "PA24(SER3:2+)_33") (pintype "bidirectional"))
    )
    (net (code "64") (name "unconnected-(U3-PA25(SER3:3+)-Pad34)") (class "Default")
      (node (ref "U3") (pin "34") (pinfunction "PA25(SER3:3+)_34") (pintype "bidirectional"))
    )
    (net (code "65") (name "unconnected-(U3-PB09(AIN3{slash}SER4:1{slash}TC4:1)-Pad8)") (class "Default")
      (node (ref "U3") (pin "8") (pinfunction "PB09(AIN3/SER4:1/TC4:1)_8") (pintype "bidirectional"))
    )
    (net (code "66") (name "unconnected-(U4-PF0-OSC_IN-Pad2)") (class "Default")
      (node (ref "U4") (pin "2") (pinfunction "PF0-OSC_IN_2") (pintype "bidirectional"))
    )
    (net (code "67") (name "unconnected-(U4-PF1-OSC_OUT-Pad3)") (class "Default")
      (node (ref "U4") (pin "3") (pinfunction "PF1-OSC_OUT_3") (pintype "bidirectional"))
    )
  )
)
